# Mini_BDM_Pod_RevA.net
KiCad netlist of a schematic drawn in EAGLE
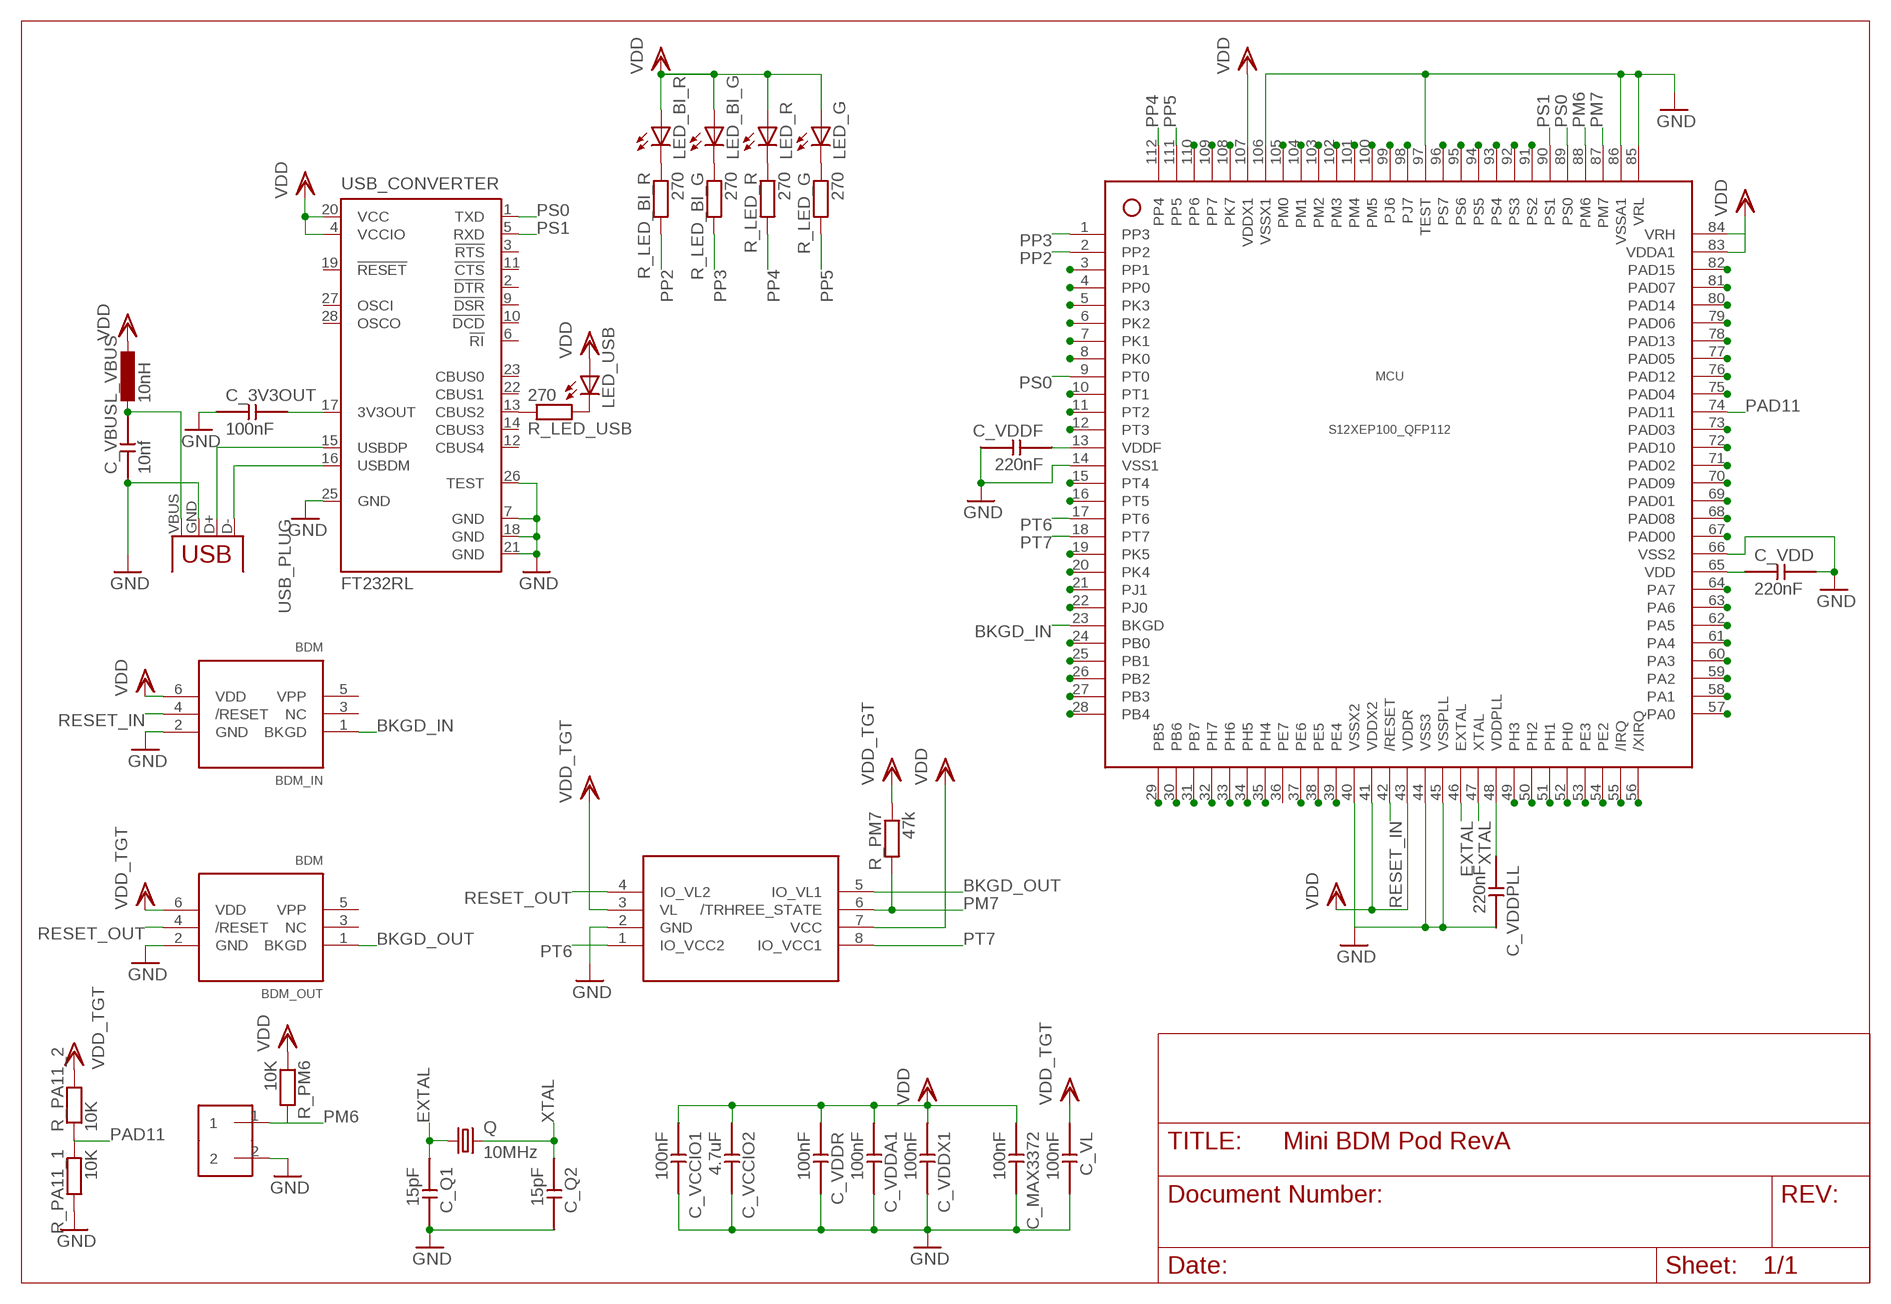
[diagram p0: schematic, sheet 1]

(export (version "E")
  (design (tool "Eeschema 10.0.6"))
  (components
    (comp (ref "BDM_IN")
      (value "BDM")
      (footprint "eagle-import:BDM")
      (libsource (lib "eagle-import") (part "BDM"))
    )
    (comp (ref "BDM_OUT")
      (value "BDM")
      (footprint "eagle-import:BDM")
      (libsource (lib "eagle-import") (part "BDM"))
    )
    (comp (ref "C_3V3OUT")
      (value "100nF")
      (footprint "eagle-import:0805")
      (libsource (lib "eagle-import") (part "C"))
    )
    (comp (ref "C_MAX3372")
      (value "100nF")
      (footprint "eagle-import:0805")
      (libsource (lib "eagle-import") (part "C"))
    )
    (comp (ref "C_Q1")
      (value "15pF")
      (footprint "eagle-import:0805")
      (libsource (lib "eagle-import") (part "C"))
    )
    (comp (ref "C_Q2")
      (value "15pF")
      (footprint "eagle-import:0805")
      (libsource (lib "eagle-import") (part "C"))
    )
    (comp (ref "C_VBUS")
      (value "10nf")
      (footprint "eagle-import:0805")
      (libsource (lib "eagle-import") (part "C"))
    )
    (comp (ref "C_VCCIO1")
      (value "100nF")
      (footprint "eagle-import:0805")
      (libsource (lib "eagle-import") (part "C"))
    )
    (comp (ref "C_VCCIO2")
      (value "4.7uF")
      (footprint "eagle-import:0805")
      (libsource (lib "eagle-import") (part "C"))
    )
    (comp (ref "C_VDD")
      (value "220nF")
      (footprint "eagle-import:0805")
      (libsource (lib "eagle-import") (part "C"))
    )
    (comp (ref "C_VDDA1")
      (value "100nF")
      (footprint "eagle-import:0805")
      (libsource (lib "eagle-import") (part "C"))
    )
    (comp (ref "C_VDDF")
      (value "220nF")
      (footprint "eagle-import:0805")
      (libsource (lib "eagle-import") (part "C"))
    )
    (comp (ref "C_VDDPLL")
      (value "220nF")
      (footprint "eagle-import:0805")
      (libsource (lib "eagle-import") (part "C"))
    )
    (comp (ref "C_VDDR")
      (value "100nF")
      (footprint "eagle-import:0805")
      (libsource (lib "eagle-import") (part "C"))
    )
    (comp (ref "C_VDDX1")
      (value "100nF")
      (footprint "eagle-import:0805")
      (libsource (lib "eagle-import") (part "C"))
    )
    (comp (ref "C_VL")
      (value "100nF")
      (footprint "eagle-import:0805")
      (libsource (lib "eagle-import") (part "C"))
    )
    (comp (ref "JUMPER")
      (value "1X2")
      (footprint "eagle-import:1X2")
      (libsource (lib "eagle-import") (part "1X2"))
    )
    (comp (ref "LED_BI_G")
      (value "LED0805")
      (footprint "eagle-import:0805")
      (libsource (lib "eagle-import") (part "LED0805"))
    )
    (comp (ref "LED_BI_R")
      (value "LED0805")
      (footprint "eagle-import:0805")
      (libsource (lib "eagle-import") (part "LED0805"))
    )
    (comp (ref "LED_G")
      (value "LED0805")
      (footprint "eagle-import:0805")
      (libsource (lib "eagle-import") (part "LED0805"))
    )
    (comp (ref "LED_R")
      (value "LED0805")
      (footprint "eagle-import:0805")
      (libsource (lib "eagle-import") (part "LED0805"))
    )
    (comp (ref "LED_USB")
      (value "LED0805")
      (footprint "eagle-import:0805")
      (libsource (lib "eagle-import") (part "LED0805"))
    )
    (comp (ref "LEVEL_SHIFTER")
      (value "MAX3373")
      (footprint "eagle-import:SOT-23-MAXIM")
      (libsource (lib "eagle-import") (part "MAX3373"))
    )
    (comp (ref "L_VBUS")
      (value "10nH")
      (footprint "eagle-import:0805")
      (libsource (lib "eagle-import") (part "L0805"))
    )
    (comp (ref "MCU")
      (value "S12XEP100_QFP112")
      (footprint "eagle-import:QFP112")
      (libsource (lib "eagle-import") (part "S12XEP100_QFP112"))
    )
    (comp (ref "Q")
      (value "10MHz")
      (footprint "eagle-import:HC49U70")
      (libsource (lib "eagle-import") (part "CRYSTALHC49U70"))
    )
    (comp (ref "R_LED_BI_G")
      (value "270")
      (footprint "eagle-import:0805")
      (libsource (lib "eagle-import") (part "R"))
    )
    (comp (ref "R_LED_BI_R")
      (value "270")
      (footprint "eagle-import:0805")
      (libsource (lib "eagle-import") (part "R"))
    )
    (comp (ref "R_LED_G")
      (value "270")
      (footprint "eagle-import:0805")
      (libsource (lib "eagle-import") (part "R"))
    )
    (comp (ref "R_LED_R")
      (value "270")
      (footprint "eagle-import:0805")
      (libsource (lib "eagle-import") (part "R"))
    )
    (comp (ref "R_LED_USB")
      (value "270")
      (footprint "eagle-import:0805")
      (libsource (lib "eagle-import") (part "R"))
    )
    (comp (ref "R_PA11_1")
      (value "10K")
      (footprint "eagle-import:0805")
      (libsource (lib "eagle-import") (part "R"))
    )
    (comp (ref "R_PA11_2")
      (value "10K")
      (footprint "eagle-import:0805")
      (libsource (lib "eagle-import") (part "R"))
    )
    (comp (ref "R_PM6")
      (value "10K")
      (footprint "eagle-import:0805")
      (libsource (lib "eagle-import") (part "R"))
    )
    (comp (ref "R_PM7")
      (value "47k")
      (footprint "eagle-import:0805")
      (libsource (lib "eagle-import") (part "R"))
    )
    (comp (ref "USB_CONVERTER")
      (value "FT232RL")
      (footprint "eagle-import:SSOP28")
      (libsource (lib "eagle-import") (part "FT232RL"))
    )
    (comp (ref "USB_PLUG")
      (value "USB_PRINT-A")
      (footprint "eagle-import:A")
      (libsource (lib "eagle-import") (part "USB_PRINT-A"))
    )
  )
  (nets
    (net (code "1") (name "/BKGD_IN") (class "Default")
      (node (ref "BDM_IN") (pin "1") (pinfunction "BKGD_1") (pintype "bidirectional"))
      (node (ref "MCU") (pin "23") (pinfunction "BKGD_23") (pintype "input"))
    )
    (net (code "2") (name "/BKGD_OUT") (class "Default")
      (node (ref "BDM_OUT") (pin "1") (pinfunction "BKGD_1") (pintype "bidirectional"))
      (node (ref "LEVEL_SHIFTER") (pin "5") (pinfunction "IO_VL1_5") (pintype "bidirectional"))
    )
    (net (code "3") (name "/EXTAL") (class "Default")
      (node (ref "C_Q1") (pin "2") (pinfunction "2_2") (pintype "passive"))
      (node (ref "MCU") (pin "46") (pinfunction "EXTAL_46") (pintype "input"))
      (node (ref "Q") (pin "1") (pinfunction "1_1") (pintype "passive"))
    )
    (net (code "4") (name "/PAD11") (class "Default")
      (node (ref "MCU") (pin "74") (pinfunction "PAD11_74") (pintype "bidirectional"))
      (node (ref "R_PA11_1") (pin "2") (pinfunction "2_2") (pintype "passive"))
      (node (ref "R_PA11_2") (pin "2") (pinfunction "2_2") (pintype "passive"))
    )
    (net (code "5") (name "/PM6") (class "Default")
      (node (ref "JUMPER") (pin "1") (pinfunction "1_1") (pintype "bidirectional"))
      (node (ref "MCU") (pin "88") (pinfunction "PM6_88") (pintype "bidirectional"))
      (node (ref "R_PM6") (pin "1") (pinfunction "1_1") (pintype "passive"))
    )
    (net (code "6") (name "/PM7") (class "Default")
      (node (ref "LEVEL_SHIFTER") (pin "6") (pinfunction "/TRHREE_STATE_6") (pintype "bidirectional"))
      (node (ref "MCU") (pin "87") (pinfunction "PM7_87") (pintype "bidirectional"))
      (node (ref "R_PM7") (pin "1") (pinfunction "1_1") (pintype "passive"))
    )
    (net (code "7") (name "/PP2") (class "Default")
      (node (ref "MCU") (pin "2") (pinfunction "PP2_2") (pintype "bidirectional"))
      (node (ref "R_LED_BI_R") (pin "1") (pinfunction "1_1") (pintype "passive"))
    )
    (net (code "8") (name "/PP3") (class "Default")
      (node (ref "MCU") (pin "1") (pinfunction "PP3_1") (pintype "bidirectional"))
      (node (ref "R_LED_BI_G") (pin "1") (pinfunction "1_1") (pintype "passive"))
    )
    (net (code "9") (name "/PP4") (class "Default")
      (node (ref "MCU") (pin "112") (pinfunction "PP4_112") (pintype "bidirectional"))
      (node (ref "R_LED_R") (pin "1") (pinfunction "1_1") (pintype "passive"))
    )
    (net (code "10") (name "/PP5") (class "Default")
      (node (ref "MCU") (pin "111") (pinfunction "PP5_111") (pintype "bidirectional"))
      (node (ref "R_LED_G") (pin "1") (pinfunction "1_1") (pintype "passive"))
    )
    (net (code "11") (name "/PS0") (class "Default")
      (node (ref "MCU") (pin "89") (pinfunction "PS0_89") (pintype "bidirectional"))
      (node (ref "MCU") (pin "9") (pinfunction "PT0_9") (pintype "bidirectional"))
      (node (ref "USB_CONVERTER") (pin "1") (pinfunction "TXD_1") (pintype "output"))
    )
    (net (code "12") (name "/PS1") (class "Default")
      (node (ref "MCU") (pin "90") (pinfunction "PS1_90") (pintype "bidirectional"))
      (node (ref "USB_CONVERTER") (pin "5") (pinfunction "RXD_5") (pintype "input"))
    )
    (net (code "13") (name "/PT6") (class "Default")
      (node (ref "LEVEL_SHIFTER") (pin "1") (pinfunction "IO_VCC2_1") (pintype "bidirectional"))
      (node (ref "MCU") (pin "17") (pinfunction "PT6_17") (pintype "bidirectional"))
    )
    (net (code "14") (name "/PT7") (class "Default")
      (node (ref "LEVEL_SHIFTER") (pin "8") (pinfunction "IO_VCC1_8") (pintype "bidirectional"))
      (node (ref "MCU") (pin "18") (pinfunction "PT7_18") (pintype "bidirectional"))
    )
    (net (code "15") (name "/RESET_IN") (class "Default")
      (node (ref "BDM_IN") (pin "4") (pinfunction "/RESET_4") (pintype "bidirectional"))
      (node (ref "MCU") (pin "42") (pinfunction "/RESET_42") (pintype "output"))
    )
    (net (code "16") (name "/RESET_OUT") (class "Default")
      (node (ref "BDM_OUT") (pin "4") (pinfunction "/RESET_4") (pintype "bidirectional"))
      (node (ref "LEVEL_SHIFTER") (pin "4") (pinfunction "IO_VL2_4") (pintype "bidirectional"))
    )
    (net (code "17") (name "/XTAL") (class "Default")
      (node (ref "C_Q2") (pin "2") (pinfunction "2_2") (pintype "passive"))
      (node (ref "MCU") (pin "47") (pinfunction "XTAL_47") (pintype "output"))
      (node (ref "Q") (pin "2") (pinfunction "2_2") (pintype "passive"))
    )
    (net (code "18") (name "GND") (class "Default")
      (node (ref "BDM_IN") (pin "2") (pinfunction "GND_2") (pintype "power_in"))
      (node (ref "BDM_OUT") (pin "2") (pinfunction "GND_2") (pintype "power_in"))
      (node (ref "C_3V3OUT") (pin "2") (pinfunction "2_2") (pintype "passive"))
      (node (ref "C_MAX3372") (pin "1") (pinfunction "1_1") (pintype "passive"))
      (node (ref "C_Q1") (pin "1") (pinfunction "1_1") (pintype "passive"))
      (node (ref "C_Q2") (pin "1") (pinfunction "1_1") (pintype "passive"))
      (node (ref "C_VBUS") (pin "2") (pinfunction "2_2") (pintype "passive"))
      (node (ref "C_VCCIO1") (pin "1") (pinfunction "1_1") (pintype "passive"))
      (node (ref "C_VCCIO2") (pin "1") (pinfunction "1_1") (pintype "passive"))
      (node (ref "C_VDD") (pin "1") (pinfunction "1_1") (pintype "passive"))
      (node (ref "C_VDDA1") (pin "1") (pinfunction "1_1") (pintype "passive"))
      (node (ref "C_VDDF") (pin "1") (pinfunction "1_1") (pintype "passive"))
      (node (ref "C_VDDPLL") (pin "1") (pinfunction "1_1") (pintype "passive"))
      (node (ref "C_VDDR") (pin "1") (pinfunction "1_1") (pintype "passive"))
      (node (ref "C_VDDX1") (pin "1") (pinfunction "1_1") (pintype "passive"))
      (node (ref "C_VL") (pin "1") (pinfunction "1_1") (pintype "passive"))
      (node (ref "JUMPER") (pin "2") (pinfunction "2_2") (pintype "bidirectional"))
      (node (ref "LEVEL_SHIFTER") (pin "2") (pinfunction "GND_2") (pintype "power_in"))
      (node (ref "MCU") (pin "106") (pinfunction "VSSX1_106") (pintype "power_in"))
      (node (ref "MCU") (pin "14") (pinfunction "VSS1_14") (pintype "power_in"))
      (node (ref "MCU") (pin "40") (pinfunction "VSSX2_40") (pintype "power_in"))
      (node (ref "MCU") (pin "44") (pinfunction "VSS3_44") (pintype "power_in"))
      (node (ref "MCU") (pin "45") (pinfunction "VSSPLL_45") (pintype "power_in"))
      (node (ref "MCU") (pin "66") (pinfunction "VSS2_66") (pintype "power_in"))
      (node (ref "MCU") (pin "85") (pinfunction "VRL_85") (pintype "power_in"))
      (node (ref "MCU") (pin "86") (pinfunction "VSSA1_86") (pintype "power_in"))
      (node (ref "MCU") (pin "97") (pinfunction "TEST_97") (pintype "input"))
      (node (ref "R_PA11_1") (pin "1") (pinfunction "1_1") (pintype "passive"))
      (node (ref "USB_CONVERTER") (pin "18") (pinfunction "GND_18") (pintype "power_in"))
      (node (ref "USB_CONVERTER") (pin "21") (pinfunction "GND_21") (pintype "power_in"))
      (node (ref "USB_CONVERTER") (pin "25") (pinfunction "GND_25") (pintype "power_in"))
      (node (ref "USB_CONVERTER") (pin "26") (pinfunction "TEST_26") (pintype "input"))
      (node (ref "USB_CONVERTER") (pin "7") (pinfunction "GND_7") (pintype "power_in"))
      (node (ref "USB_PLUG") (pin "GND") (pinfunction "VBUS_GND") (pintype "bidirectional"))
    )
    (net (code "19") (name "Net-(LED_BI_G-C)") (class "Default")
      (node (ref "LED_BI_G") (pin "2") (pinfunction "C_2") (pintype "passive"))
      (node (ref "R_LED_BI_G") (pin "2") (pinfunction "2_2") (pintype "passive"))
    )
    (net (code "20") (name "Net-(LED_BI_R-C)") (class "Default")
      (node (ref "LED_BI_R") (pin "2") (pinfunction "C_2") (pintype "passive"))
      (node (ref "R_LED_BI_R") (pin "2") (pinfunction "2_2") (pintype "passive"))
    )
    (net (code "21") (name "Net-(LED_G-C)") (class "Default")
      (node (ref "LED_G") (pin "2") (pinfunction "C_2") (pintype "passive"))
      (node (ref "R_LED_G") (pin "2") (pinfunction "2_2") (pintype "passive"))
    )
    (net (code "22") (name "Net-(LED_R-C)") (class "Default")
      (node (ref "LED_R") (pin "2") (pinfunction "C_2") (pintype "passive"))
      (node (ref "R_LED_R") (pin "2") (pinfunction "2_2") (pintype "passive"))
    )
    (net (code "23") (name "Net-(LED_USB-C)") (class "Default")
      (node (ref "LED_USB") (pin "2") (pinfunction "C_2") (pintype "passive"))
      (node (ref "R_LED_USB") (pin "1") (pinfunction "1_1") (pintype "passive"))
    )
    (net (code "24") (name "Net-(MCU-VDD)") (class "Default")
      (node (ref "C_VDD") (pin "2") (pinfunction "2_2") (pintype "passive"))
      (node (ref "MCU") (pin "65") (pinfunction "VDD_65") (pintype "power_in"))
    )
    (net (code "25") (name "Net-(MCU-VDDF)") (class "Default")
      (node (ref "C_VDDF") (pin "2") (pinfunction "2_2") (pintype "passive"))
      (node (ref "MCU") (pin "13") (pinfunction "VDDF_13") (pintype "power_in"))
    )
    (net (code "26") (name "Net-(MCU-VDDPLL)") (class "Default")
      (node (ref "C_VDDPLL") (pin "2") (pinfunction "2_2") (pintype "passive"))
      (node (ref "MCU") (pin "48") (pinfunction "VDDPLL_48") (pintype "power_in"))
    )
    (net (code "27") (name "Net-(USB_CONVERTER-3V3OUT)") (class "Default")
      (node (ref "C_3V3OUT") (pin "1") (pinfunction "1_1") (pintype "passive"))
      (node (ref "USB_CONVERTER") (pin "17") (pinfunction "3V3OUT_17") (pintype "output"))
    )
    (net (code "28") (name "Net-(USB_CONVERTER-CBUS2)") (class "Default")
      (node (ref "R_LED_USB") (pin "2") (pinfunction "2_2") (pintype "passive"))
      (node (ref "USB_CONVERTER") (pin "13") (pinfunction "CBUS2_13") (pintype "bidirectional"))
    )
    (net (code "29") (name "Net-(USB_CONVERTER-USBDM)") (class "Default")
      (node (ref "USB_CONVERTER") (pin "16") (pinfunction "USBDM_16") (pintype "bidirectional"))
      (node (ref "USB_PLUG") (pin "D-") (pinfunction "D+_D-") (pintype "bidirectional"))
    )
    (net (code "30") (name "Net-(USB_CONVERTER-USBDP)") (class "Default")
      (node (ref "USB_CONVERTER") (pin "15") (pinfunction "USBDP_15") (pintype "bidirectional"))
      (node (ref "USB_PLUG") (pin "D+") (pinfunction "D-_D+") (pintype "bidirectional"))
    )
    (net (code "31") (name "Net-(USB_PLUG-GND)") (class "Default")
      (node (ref "C_VBUS") (pin "1") (pinfunction "1_1") (pintype "passive"))
      (node (ref "L_VBUS") (pin "2") (pinfunction "2_2") (pintype "passive"))
      (node (ref "USB_PLUG") (pin "VBUS") (pinfunction "GND_VBUS") (pintype "bidirectional"))
    )
    (net (code "32") (name "VDD") (class "Default")
      (node (ref "BDM_IN") (pin "6") (pinfunction "VDD_6") (pintype "power_in"))
      (node (ref "C_MAX3372") (pin "2") (pinfunction "2_2") (pintype "passive"))
      (node (ref "C_VCCIO1") (pin "2") (pinfunction "2_2") (pintype "passive"))
      (node (ref "C_VCCIO2") (pin "2") (pinfunction "2_2") (pintype "passive"))
      (node (ref "C_VDDA1") (pin "2") (pinfunction "2_2") (pintype "passive"))
      (node (ref "C_VDDR") (pin "2") (pinfunction "2_2") (pintype "passive"))
      (node (ref "C_VDDX1") (pin "2") (pinfunction "2_2") (pintype "passive"))
      (node (ref "LED_BI_G") (pin "1") (pinfunction "A_1") (pintype "passive"))
      (node (ref "LED_BI_R") (pin "1") (pinfunction "A_1") (pintype "passive"))
      (node (ref "LED_G") (pin "1") (pinfunction "A_1") (pintype "passive"))
      (node (ref "LED_R") (pin "1") (pinfunction "A_1") (pintype "passive"))
      (node (ref "LED_USB") (pin "1") (pinfunction "A_1") (pintype "passive"))
      (node (ref "LEVEL_SHIFTER") (pin "7") (pinfunction "VCC_7") (pintype "power_in"))
      (node (ref "L_VBUS") (pin "1") (pinfunction "1_1") (pintype "passive"))
      (node (ref "MCU") (pin "107") (pinfunction "VDDX1_107") (pintype "power_in"))
      (node (ref "MCU") (pin "41") (pinfunction "VDDX2_41") (pintype "power_in"))
      (node (ref "MCU") (pin "43") (pinfunction "VDDR_43") (pintype "power_in"))
      (node (ref "MCU") (pin "83") (pinfunction "VDDA1_83") (pintype "power_in"))
      (node (ref "MCU") (pin "84") (pinfunction "VRH_84") (pintype "power_in"))
      (node (ref "R_PM6") (pin "2") (pinfunction "2_2") (pintype "passive"))
      (node (ref "USB_CONVERTER") (pin "20") (pinfunction "VCC_20") (pintype "power_in"))
      (node (ref "USB_CONVERTER") (pin "4") (pinfunction "VCCIO_4") (pintype "power_in"))
    )
    (net (code "33") (name "VDD_TGT") (class "Default")
      (node (ref "BDM_OUT") (pin "6") (pinfunction "VDD_6") (pintype "power_in"))
      (node (ref "C_VL") (pin "2") (pinfunction "2_2") (pintype "passive"))
      (node (ref "LEVEL_SHIFTER") (pin "3") (pinfunction "VL_3") (pintype "bidirectional"))
      (node (ref "R_PA11_2") (pin "1") (pinfunction "1_1") (pintype "passive"))
      (node (ref "R_PM7") (pin "2") (pinfunction "2_2") (pintype "passive"))
    )
    (net (code "34") (name "unconnected-(BDM_IN-NC-Pad3)") (class "Default")
      (node (ref "BDM_IN") (pin "3") (pinfunction "NC_3") (pintype "no_connect"))
    )
    (net (code "35") (name "unconnected-(BDM_IN-VPP-Pad5)") (class "Default")
      (node (ref "BDM_IN") (pin "5") (pinfunction "VPP_5") (pintype "no_connect"))
    )
    (net (code "36") (name "unconnected-(BDM_OUT-NC-Pad3)") (class "Default")
      (node (ref "BDM_OUT") (pin "3") (pinfunction "NC_3") (pintype "no_connect"))
    )
    (net (code "37") (name "unconnected-(BDM_OUT-VPP-Pad5)") (class "Default")
      (node (ref "BDM_OUT") (pin "5") (pinfunction "VPP_5") (pintype "no_connect"))
    )
    (net (code "38") (name "unconnected-(MCU-PA0-Pad57)") (class "Default")
      (node (ref "MCU") (pin "57") (pinfunction "PA0_57") (pintype "bidirectional"))
    )
    (net (code "39") (name "unconnected-(MCU-PA1-Pad58)") (class "Default")
      (node (ref "MCU") (pin "58") (pinfunction "PA1_58") (pintype "bidirectional"))
    )
    (net (code "40") (name "unconnected-(MCU-PA2-Pad59)") (class "Default")
      (node (ref "MCU") (pin "59") (pinfunction "PA2_59") (pintype "bidirectional"))
    )
    (net (code "41") (name "unconnected-(MCU-PA3-Pad60)") (class "Default")
      (node (ref "MCU") (pin "60") (pinfunction "PA3_60") (pintype "bidirectional"))
    )
    (net (code "42") (name "unconnected-(MCU-PA4-Pad61)") (class "Default")
      (node (ref "MCU") (pin "61") (pinfunction "PA4_61") (pintype "bidirectional"))
    )
    (net (code "43") (name "unconnected-(MCU-PA5-Pad62)") (class "Default")
      (node (ref "MCU") (pin "62") (pinfunction "PA5_62") (pintype "bidirectional"))
    )
    (net (code "44") (name "unconnected-(MCU-PA6-Pad63)") (class "Default")
      (node (ref "MCU") (pin "63") (pinfunction "PA6_63") (pintype "bidirectional"))
    )
    (net (code "45") (name "unconnected-(MCU-PA7-Pad64)") (class "Default")
      (node (ref "MCU") (pin "64") (pinfunction "PA7_64") (pintype "bidirectional"))
    )
    (net (code "46") (name "unconnected-(MCU-PAD00-Pad67)") (class "Default")
      (node (ref "MCU") (pin "67") (pinfunction "PAD00_67") (pintype "bidirectional"))
    )
    (net (code "47") (name "unconnected-(MCU-PAD01-Pad69)") (class "Default")
      (node (ref "MCU") (pin "69") (pinfunction "PAD01_69") (pintype "bidirectional"))
    )
    (net (code "48") (name "unconnected-(MCU-PAD02-Pad71)") (class "Default")
      (node (ref "MCU") (pin "71") (pinfunction "PAD02_71") (pintype "bidirectional"))
    )
    (net (code "49") (name "unconnected-(MCU-PAD03-Pad73)") (class "Default")
      (node (ref "MCU") (pin "73") (pinfunction "PAD03_73") (pintype "bidirectional"))
    )
    (net (code "50") (name "unconnected-(MCU-PAD04-Pad75)") (class "Default")
      (node (ref "MCU") (pin "75") (pinfunction "PAD04_75") (pintype "bidirectional"))
    )
    (net (code "51") (name "unconnected-(MCU-PAD05-Pad77)") (class "Default")
      (node (ref "MCU") (pin "77") (pinfunction "PAD05_77") (pintype "bidirectional"))
    )
    (net (code "52") (name "unconnected-(MCU-PAD06-Pad79)") (class "Default")
      (node (ref "MCU") (pin "79") (pinfunction "PAD06_79") (pintype "bidirectional"))
    )
    (net (code "53") (name "unconnected-(MCU-PAD07-Pad81)") (class "Default")
      (node (ref "MCU") (pin "81") (pinfunction "PAD07_81") (pintype "bidirectional"))
    )
    (net (code "54") (name "unconnected-(MCU-PAD08-Pad68)") (class "Default")
      (node (ref "MCU") (pin "68") (pinfunction "PAD08_68") (pintype "bidirectional"))
    )
    (net (code "55") (name "unconnected-(MCU-PAD09-Pad70)") (class "Default")
      (node (ref "MCU") (pin "70") (pinfunction "PAD09_70") (pintype "bidirectional"))
    )
    (net (code "56") (name "unconnected-(MCU-PAD10-Pad72)") (class "Default")
      (node (ref "MCU") (pin "72") (pinfunction "PAD10_72") (pintype "bidirectional"))
    )
    (net (code "57") (name "unconnected-(MCU-PAD12-Pad76)") (class "Default")
      (node (ref "MCU") (pin "76") (pinfunction "PAD12_76") (pintype "bidirectional"))
    )
    (net (code "58") (name "unconnected-(MCU-PAD13-Pad78)") (class "Default")
      (node (ref "MCU") (pin "78") (pinfunction "PAD13_78") (pintype "bidirectional"))
    )
    (net (code "59") (name "unconnected-(MCU-PAD14-Pad80)") (class "Default")
      (node (ref "MCU") (pin "80") (pinfunction "PAD14_80") (pintype "bidirectional"))
    )
    (net (code "60") (name "unconnected-(MCU-PAD15-Pad82)") (class "Default")
      (node (ref "MCU") (pin "82") (pinfunction "PAD15_82") (pintype "bidirectional"))
    )
    (net (code "61") (name "unconnected-(MCU-PB0-Pad24)") (class "Default")
      (node (ref "MCU") (pin "24") (pinfunction "PB0_24") (pintype "bidirectional"))
    )
    (net (code "62") (name "unconnected-(MCU-PB1-Pad25)") (class "Default")
      (node (ref "MCU") (pin "25") (pinfunction "PB1_25") (pintype "bidirectional"))
    )
    (net (code "63") (name "unconnected-(MCU-PB2-Pad26)") (class "Default")
      (node (ref "MCU") (pin "26") (pinfunction "PB2_26") (pintype "bidirectional"))
    )
    (net (code "64") (name "unconnected-(MCU-PB3-Pad27)") (class "Default")
      (node (ref "MCU") (pin "27") (pinfunction "PB3_27") (pintype "bidirectional"))
    )
    (net (code "65") (name "unconnected-(MCU-PB4-Pad28)") (class "Default")
      (node (ref "MCU") (pin "28") (pinfunction "PB4_28") (pintype "bidirectional"))
    )
    (net (code "66") (name "unconnected-(MCU-PB5-Pad29)") (class "Default")
      (node (ref "MCU") (pin "29") (pinfunction "PB5_29") (pintype "bidirectional"))
    )
    (net (code "67") (name "unconnected-(MCU-PB6-Pad30)") (class "Default")
      (node (ref "MCU") (pin "30") (pinfunction "PB6_30") (pintype "bidirectional"))
    )
    (net (code "68") (name "unconnected-(MCU-PB7-Pad31)") (class "Default")
      (node (ref "MCU") (pin "31") (pinfunction "PB7_31") (pintype "bidirectional"))
    )
    (net (code "69") (name "unconnected-(MCU-PE2-Pad54)") (class "Default")
      (node (ref "MCU") (pin "54") (pinfunction "PE2_54") (pintype "bidirectional"))
    )
    (net (code "70") (name "unconnected-(MCU-PE3-Pad53)") (class "Default")
      (node (ref "MCU") (pin "53") (pinfunction "PE3_53") (pintype "bidirectional"))
    )
    (net (code "71") (name "unconnected-(MCU-PE4-Pad39)") (class "Default")
      (node (ref "MCU") (pin "39") (pinfunction "PE4_39") (pintype "bidirectional"))
    )
    (net (code "72") (name "unconnected-(MCU-PE5-Pad38)") (class "Default")
      (node (ref "MCU") (pin "38") (pinfunction "PE5_38") (pintype "bidirectional"))
    )
    (net (code "73") (name "unconnected-(MCU-PE6-Pad37)") (class "Default")
      (node (ref "MCU") (pin "37") (pinfunction "PE6_37") (pintype "bidirectional"))
    )
    (net (code "74") (name "unconnected-(MCU-PE7-Pad36)") (class "Default")
      (node (ref "MCU") (pin "36") (pinfunction "PE7_36") (pintype "bidirectional"))
    )
    (net (code "75") (name "unconnected-(MCU-PH0-Pad52)") (class "Default")
      (node (ref "MCU") (pin "52") (pinfunction "PH0_52") (pintype "bidirectional"))
    )
    (net (code "76") (name "unconnected-(MCU-PH1-Pad51)") (class "Default")
      (node (ref "MCU") (pin "51") (pinfunction "PH1_51") (pintype "bidirectional"))
    )
    (net (code "77") (name "unconnected-(MCU-PH2-Pad50)") (class "Default")
      (node (ref "MCU") (pin "50") (pinfunction "PH2_50") (pintype "bidirectional"))
    )
    (net (code "78") (name "unconnected-(MCU-PH3-Pad49)") (class "Default")
      (node (ref "MCU") (pin "49") (pinfunction "PH3_49") (pintype "bidirectional"))
    )
    (net (code "79") (name "unconnected-(MCU-PH4-Pad35)") (class "Default")
      (node (ref "MCU") (pin "35") (pinfunction "PH4_35") (pintype "bidirectional"))
    )
    (net (code "80") (name "unconnected-(MCU-PH5-Pad34)") (class "Default")
      (node (ref "MCU") (pin "34") (pinfunction "PH5_34") (pintype "bidirectional"))
    )
    (net (code "81") (name "unconnected-(MCU-PH6-Pad33)") (class "Default")
      (node (ref "MCU") (pin "33") (pinfunction "PH6_33") (pintype "bidirectional"))
    )
    (net (code "82") (name "unconnected-(MCU-PH7-Pad32)") (class "Default")
      (node (ref "MCU") (pin "32") (pinfunction "PH7_32") (pintype "bidirectional"))
    )
    (net (code "83") (name "unconnected-(MCU-PJ0-Pad22)") (class "Default")
      (node (ref "MCU") (pin "22") (pinfunction "PJ0_22") (pintype "bidirectional"))
    )
    (net (code "84") (name "unconnected-(MCU-PJ1-Pad21)") (class "Default")
      (node (ref "MCU") (pin "21") (pinfunction "PJ1_21") (pintype "bidirectional"))
    )
    (net (code "85") (name "unconnected-(MCU-PJ6-Pad99)") (class "Default")
      (node (ref "MCU") (pin "99") (pinfunction "PJ6_99") (pintype "bidirectional"))
    )
    (net (code "86") (name "unconnected-(MCU-PJ7-Pad98)") (class "Default")
      (node (ref "MCU") (pin "98") (pinfunction "PJ7_98") (pintype "bidirectional"))
    )
    (net (code "87") (name "unconnected-(MCU-PK0-Pad8)") (class "Default")
      (node (ref "MCU") (pin "8") (pinfunction "PK0_8") (pintype "bidirectional"))
    )
    (net (code "88") (name "unconnected-(MCU-PK1-Pad7)") (class "Default")
      (node (ref "MCU") (pin "7") (pinfunction "PK1_7") (pintype "bidirectional"))
    )
    (net (code "89") (name "unconnected-(MCU-PK2-Pad6)") (class "Default")
      (node (ref "MCU") (pin "6") (pinfunction "PK2_6") (pintype "bidirectional"))
    )
    (net (code "90") (name "unconnected-(MCU-PK3-Pad5)") (class "Default")
      (node (ref "MCU") (pin "5") (pinfunction "PK3_5") (pintype "bidirectional"))
    )
    (net (code "91") (name "unconnected-(MCU-PK4-Pad20)") (class "Default")
      (node (ref "MCU") (pin "20") (pinfunction "PK4_20") (pintype "bidirectional"))
    )
    (net (code "92") (name "unconnected-(MCU-PK5-Pad19)") (class "Default")
      (node (ref "MCU") (pin "19") (pinfunction "PK5_19") (pintype "bidirectional"))
    )
    (net (code "93") (name "unconnected-(MCU-PK7-Pad108)") (class "Default")
      (node (ref "MCU") (pin "108") (pinfunction "PK7_108") (pintype "bidirectional"))
    )
    (net (code "94") (name "unconnected-(MCU-PM0-Pad105)") (class "Default")
      (node (ref "MCU") (pin "105") (pinfunction "PM0_105") (pintype "bidirectional"))
    )
    (net (code "95") (name "unconnected-(MCU-PM1-Pad104)") (class "Default")
      (node (ref "MCU") (pin "104") (pinfunction "PM1_104") (pintype "bidirectional"))
    )
    (net (code "96") (name "unconnected-(MCU-PM2-Pad103)") (class "Default")
      (node (ref "MCU") (pin "103") (pinfunction "PM2_103") (pintype "bidirectional"))
    )
    (net (code "97") (name "unconnected-(MCU-PM3-Pad102)") (class "Default")
      (node (ref "MCU") (pin "102") (pinfunction "PM3_102") (pintype "bidirectional"))
    )
    (net (code "98") (name "unconnected-(MCU-PM4-Pad101)") (class "Default")
      (node (ref "MCU") (pin "101") (pinfunction "PM4_101") (pintype "bidirectional"))
    )
    (net (code "99") (name "unconnected-(MCU-PM5-Pad100)") (class "Default")
      (node (ref "MCU") (pin "100") (pinfunction "PM5_100") (pintype "bidirectional"))
    )
    (net (code "100") (name "unconnected-(MCU-PP0-Pad4)") (class "Default")
      (node (ref "MCU") (pin "4") (pinfunction "PP0_4") (pintype "bidirectional"))
    )
    (net (code "101") (name "unconnected-(MCU-PP1-Pad3)") (class "Default")
      (node (ref "MCU") (pin "3") (pinfunction "PP1_3") (pintype "bidirectional"))
    )
    (net (code "102") (name "unconnected-(MCU-PP6-Pad110)") (class "Default")
      (node (ref "MCU") (pin "110") (pinfunction "PP6_110") (pintype "bidirectional"))
    )
    (net (code "103") (name "unconnected-(MCU-PP7-Pad109)") (class "Default")
      (node (ref "MCU") (pin "109") (pinfunction "PP7_109") (pintype "bidirectional"))
    )
    (net (code "104") (name "unconnected-(MCU-PS2-Pad91)") (class "Default")
      (node (ref "MCU") (pin "91") (pinfunction "PS2_91") (pintype "bidirectional"))
    )
    (net (code "105") (name "unconnected-(MCU-PS3-Pad92)") (class "Default")
      (node (ref "MCU") (pin "92") (pinfunction "PS3_92") (pintype "bidirectional"))
    )
    (net (code "106") (name "unconnected-(MCU-PS4-Pad93)") (class "Default")
      (node (ref "MCU") (pin "93") (pinfunction "PS4_93") (pintype "bidirectional"))
    )
    (net (code "107") (name "unconnected-(MCU-PS5-Pad94)") (class "Default")
      (node (ref "MCU") (pin "94") (pinfunction "PS5_94") (pintype "bidirectional"))
    )
    (net (code "108") (name "unconnected-(MCU-PS6-Pad95)") (class "Default")
      (node (ref "MCU") (pin "95") (pinfunction "PS6_95") (pintype "bidirectional"))
    )
    (net (code "109") (name "unconnected-(MCU-PS7-Pad96)") (class "Default")
      (node (ref "MCU") (pin "96") (pinfunction "PS7_96") (pintype "bidirectional"))
    )
    (net (code "110") (name "unconnected-(MCU-PT1-Pad10)") (class "Default")
      (node (ref "MCU") (pin "10") (pinfunction "PT1_10") (pintype "bidirectional"))
    )
    (net (code "111") (name "unconnected-(MCU-PT2-Pad11)") (class "Default")
      (node (ref "MCU") (pin "11") (pinfunction "PT2_11") (pintype "bidirectional"))
    )
    (net (code "112") (name "unconnected-(MCU-PT3-Pad12)") (class "Default")
      (node (ref "MCU") (pin "12") (pinfunction "PT3_12") (pintype "bidirectional"))
    )
    (net (code "113") (name "unconnected-(MCU-PT4-Pad15)") (class "Default")
      (node (ref "MCU") (pin "15") (pinfunction "PT4_15") (pintype "bidirectional"))
    )
    (net (code "114") (name "unconnected-(MCU-PT5-Pad16)") (class "Default")
      (node (ref "MCU") (pin "16") (pinfunction "PT5_16") (pintype "bidirectional"))
    )
    (net (code "115") (name "unconnected-(MCU-{slash}IRQ-Pad55)") (class "Default")
      (node (ref "MCU") (pin "55") (pinfunction "/IRQ_55") (pintype "bidirectional"))
    )
    (net (code "116") (name "unconnected-(MCU-{slash}XIRQ-Pad56)") (class "Default")
      (node (ref "MCU") (pin "56") (pinfunction "/XIRQ_56") (pintype "bidirectional"))
    )
    (net (code "117") (name "unconnected-(USB_CONVERTER-CBUS0-Pad23)") (class "Default")
      (node (ref "USB_CONVERTER") (pin "23") (pinfunction "CBUS0_23") (pintype "bidirectional"))
    )
    (net (code "118") (name "unconnected-(USB_CONVERTER-CBUS1-Pad22)") (class "Default")
      (node (ref "USB_CONVERTER") (pin "22") (pinfunction "CBUS1_22") (pintype "bidirectional"))
    )
    (net (code "119") (name "unconnected-(USB_CONVERTER-CBUS3-Pad14)") (class "Default")
      (node (ref "USB_CONVERTER") (pin "14") (pinfunction "CBUS3_14") (pintype "bidirectional"))
    )
    (net (code "120") (name "unconnected-(USB_CONVERTER-CBUS4-Pad12)") (class "Default")
      (node (ref "USB_CONVERTER") (pin "12") (pinfunction "CBUS4_12") (pintype "bidirectional"))
    )
    (net (code "121") (name "unconnected-(USB_CONVERTER-OSCI-Pad27)") (class "Default")
      (node (ref "USB_CONVERTER") (pin "27") (pinfunction "OSCI_27") (pintype "input"))
    )
    (net (code "122") (name "unconnected-(USB_CONVERTER-OSCO-Pad28)") (class "Default")
      (node (ref "USB_CONVERTER") (pin "28") (pinfunction "OSCO_28") (pintype "output"))
    )
    (net (code "123") (name "unconnected-(USB_CONVERTER-~{CTS}-Pad11)") (class "Default")
      (node (ref "USB_CONVERTER") (pin "11") (pinfunction "~{CTS}_11") (pintype "input"))
    )
    (net (code "124") (name "unconnected-(USB_CONVERTER-~{DCD}-Pad10)") (class "Default")
      (node (ref "USB_CONVERTER") (pin "10") (pinfunction "~{DCD}_10") (pintype "input"))
    )
    (net (code "125") (name "unconnected-(USB_CONVERTER-~{DSR}-Pad9)") (class "Default")
      (node (ref "USB_CONVERTER") (pin "9") (pinfunction "~{DSR}_9") (pintype "input"))
    )
    (net (code "126") (name "unconnected-(USB_CONVERTER-~{DTR}-Pad2)") (class "Default")
      (node (ref "USB_CONVERTER") (pin "2") (pinfunction "~{DTR}_2") (pintype "output"))
    )
    (net (code "127") (name "unconnected-(USB_CONVERTER-~{RESET}-Pad19)") (class "Default")
      (node (ref "USB_CONVERTER") (pin "19") (pinfunction "~{RESET}_19") (pintype "input"))
    )
    (net (code "128") (name "unconnected-(USB_CONVERTER-~{RI}-Pad6)") (class "Default")
      (node (ref "USB_CONVERTER") (pin "6") (pinfunction "~{RI}_6") (pintype "input"))
    )
    (net (code "129") (name "unconnected-(USB_CONVERTER-~{RTS}-Pad3)") (class "Default")
      (node (ref "USB_CONVERTER") (pin "3") (pinfunction "~{RTS}_3") (pintype "output"))
    )
  )
)
